# optical_meter_reader_v3.net
KiCad netlist of a schematic drawn in EAGLE
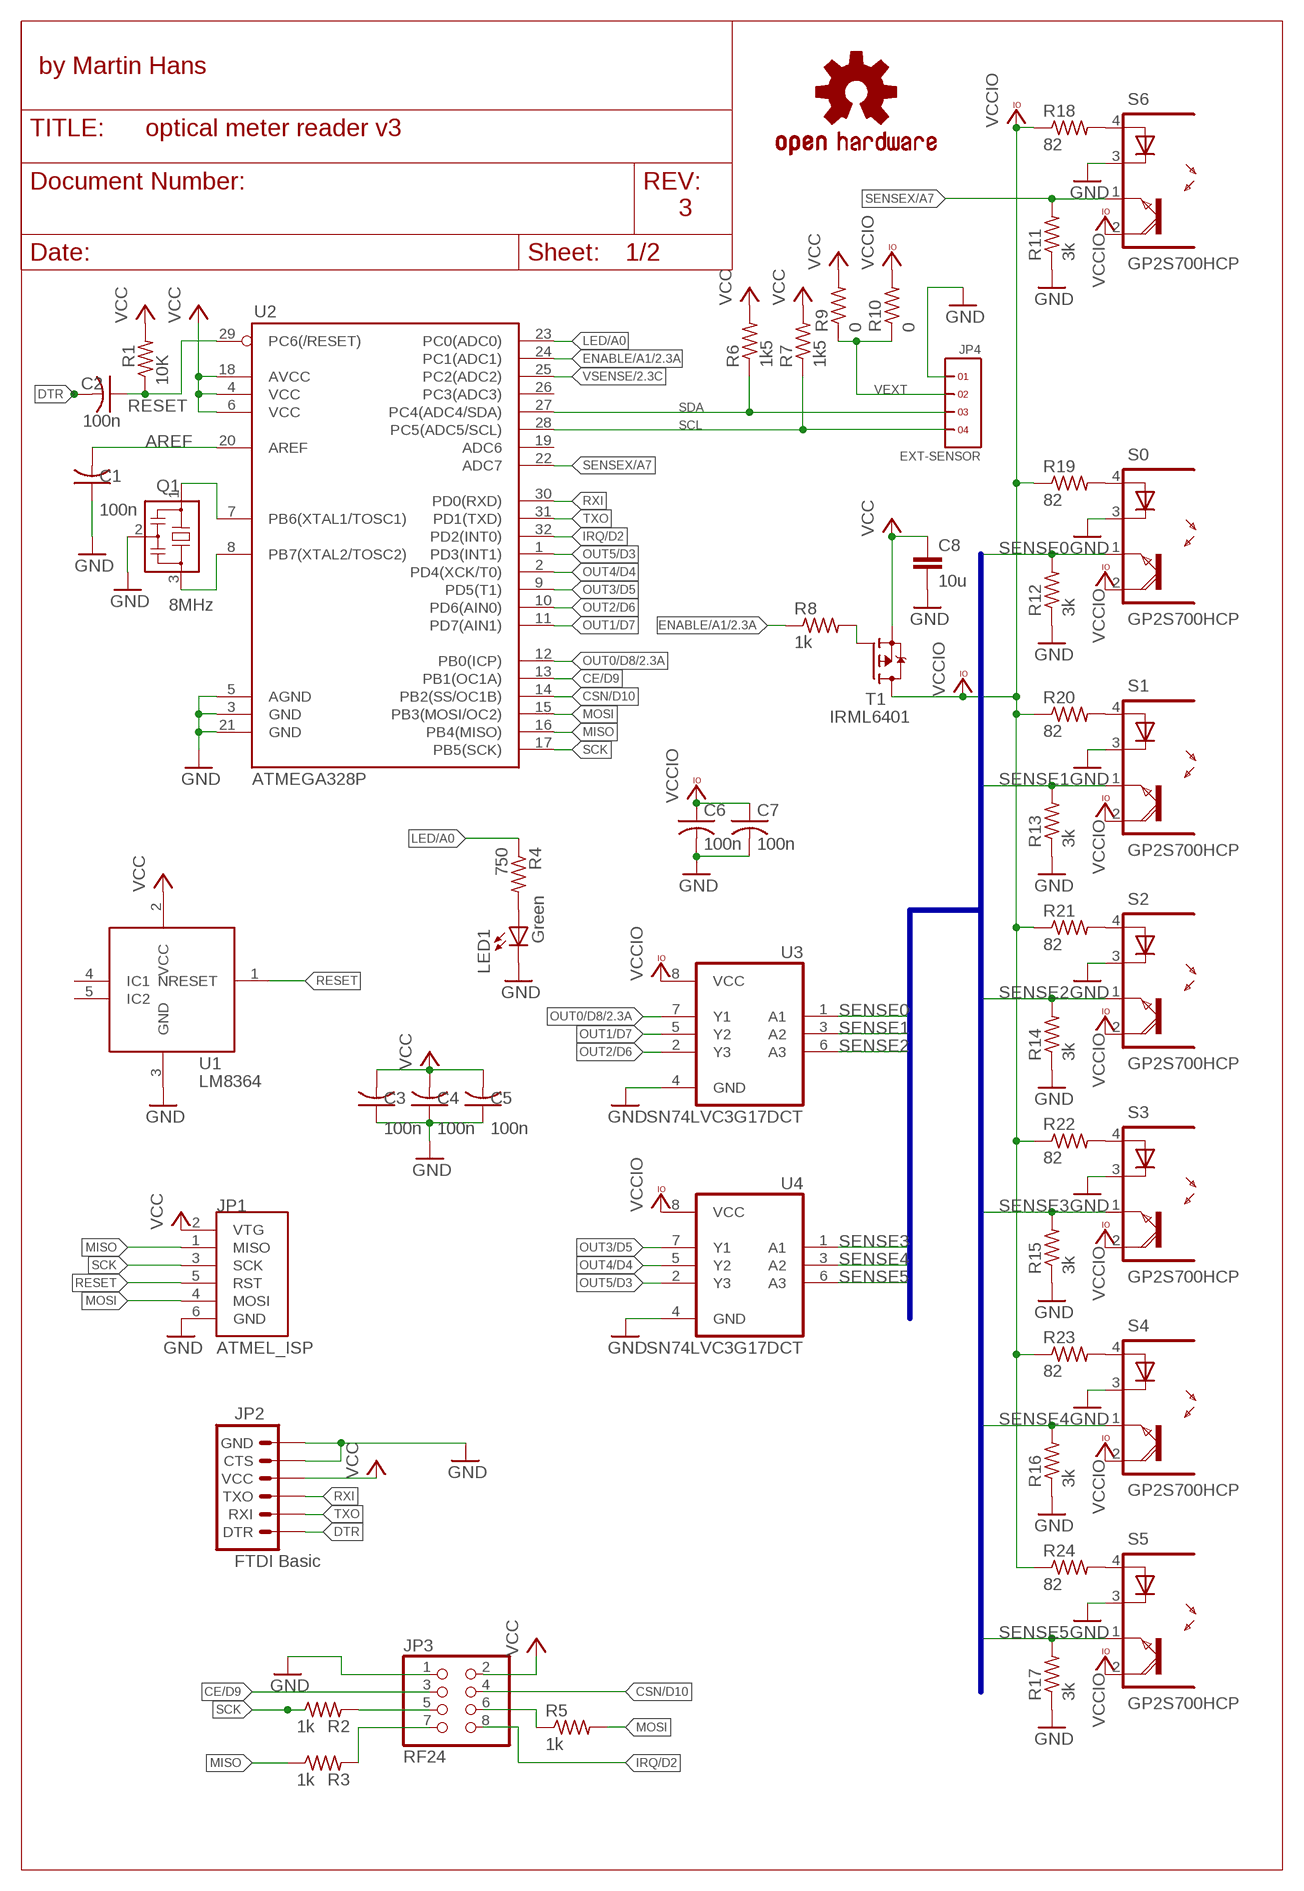
[diagram p0: schematic, sheet 1]
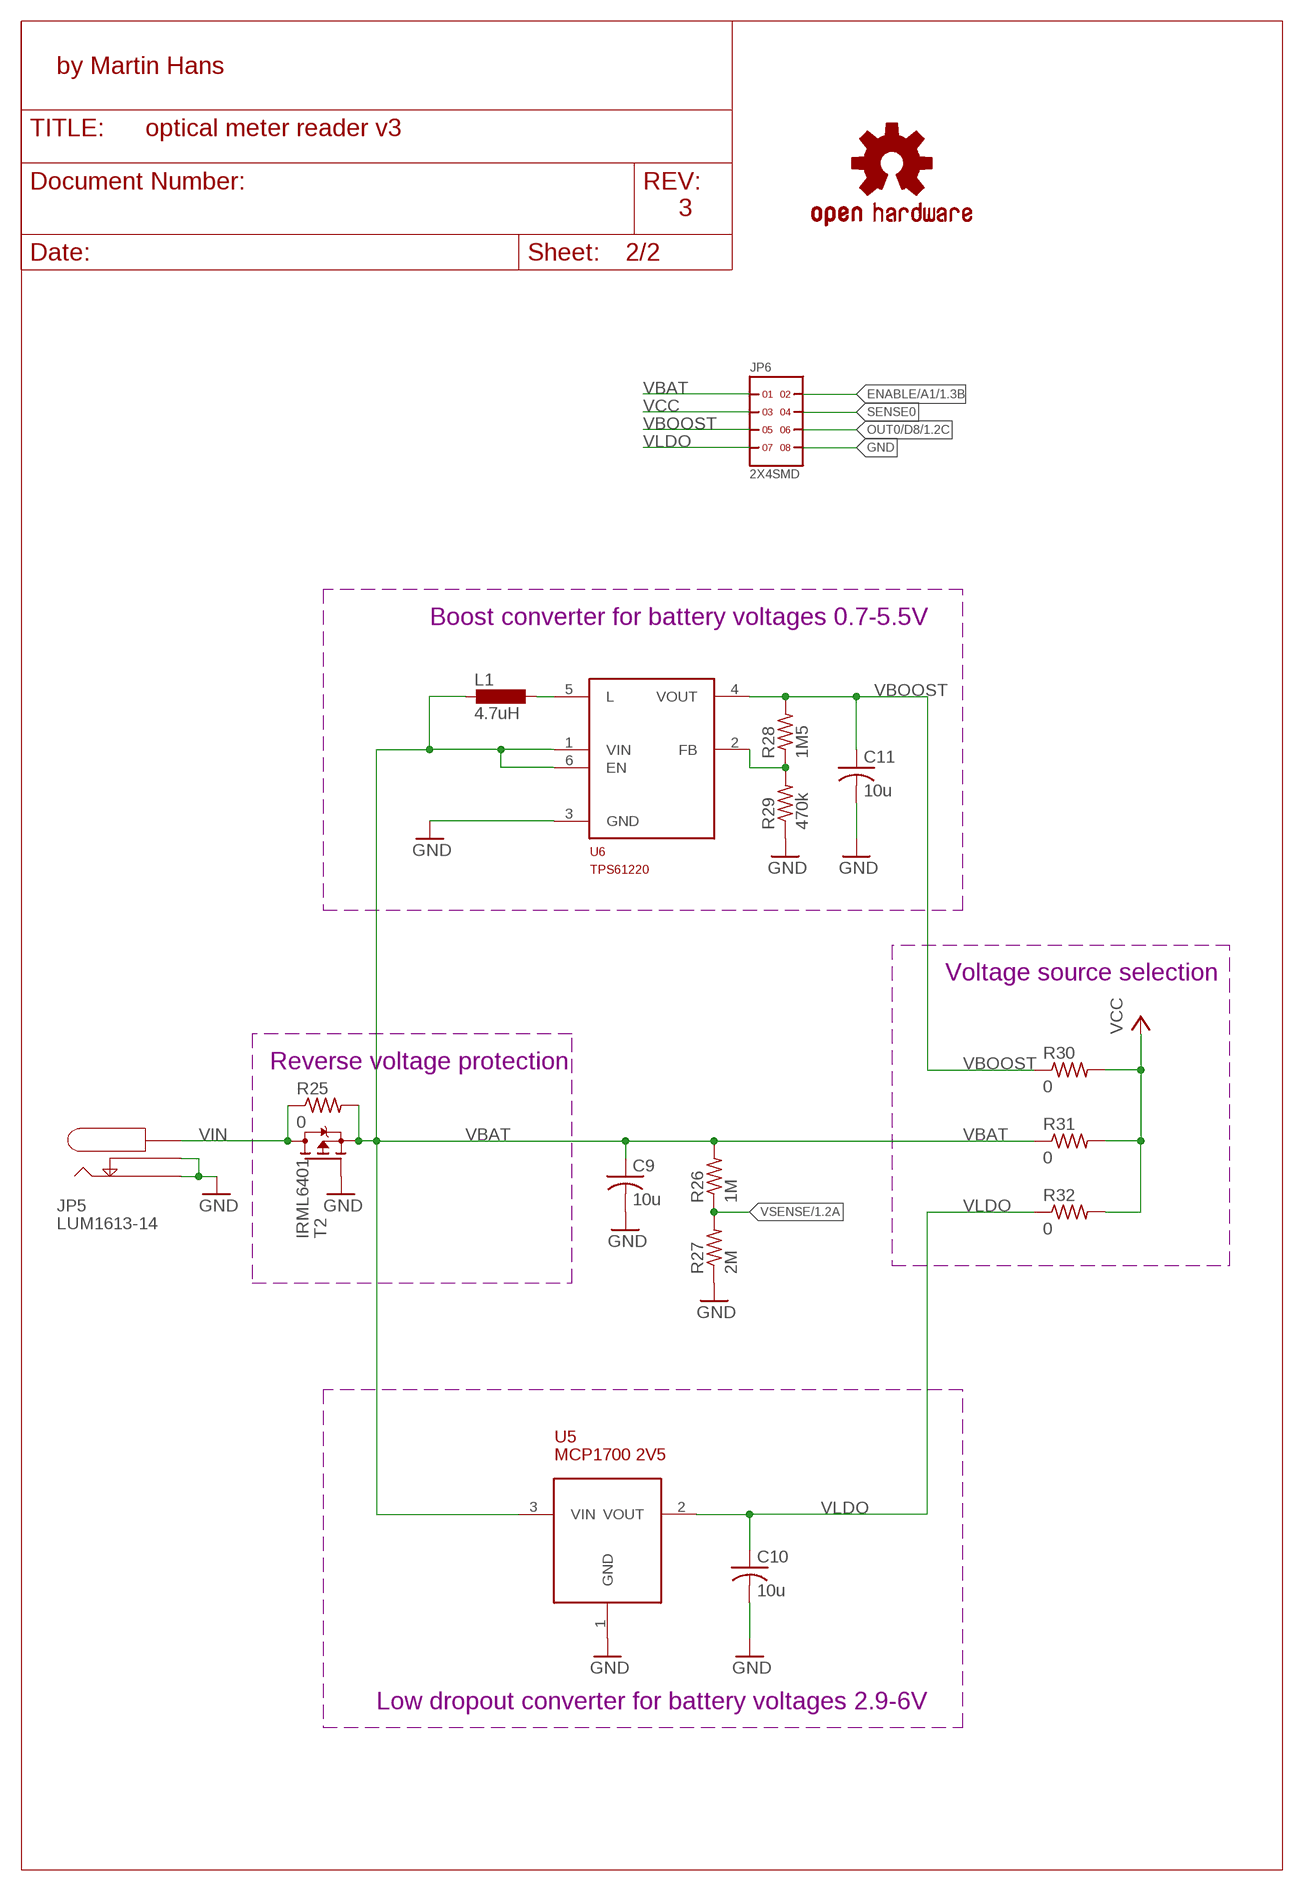
[diagram p1: schematic, sheet 2]

(export (version "E")
  (design (tool "Eeschema 10.0.6"))
  (components
    (comp (ref "C1")
      (value "100n")
      (footprint "eagle-import:C0603")
      (libsource (lib "eagle-import") (part "rcl_C-USC0603"))
    )
    (comp (ref "C2")
      (value "100n")
      (footprint "eagle-import:C0603")
      (libsource (lib "eagle-import") (part "rcl_C-USC0603"))
    )
    (comp (ref "C3")
      (value "100n")
      (footprint "eagle-import:C0603")
      (libsource (lib "eagle-import") (part "rcl_C-USC0603"))
    )
    (comp (ref "C4")
      (value "100n")
      (footprint "eagle-import:C0603")
      (libsource (lib "eagle-import") (part "rcl_C-USC0603"))
    )
    (comp (ref "C5")
      (value "100n")
      (footprint "eagle-import:C0603")
      (libsource (lib "eagle-import") (part "rcl_C-USC0603"))
    )
    (comp (ref "C6")
      (value "100n")
      (footprint "eagle-import:C0603")
      (libsource (lib "eagle-import") (part "rcl_C-USC0603"))
    )
    (comp (ref "C7")
      (value "100n")
      (footprint "eagle-import:C0603")
      (libsource (lib "eagle-import") (part "rcl_C-USC0603"))
    )
    (comp (ref "C8")
      (value "10u")
      (footprint "eagle-import:C0603")
      (libsource (lib "eagle-import") (part "C-EUC0603"))
    )
    (comp (ref "JP1")
      (value "ATMEL_ISP")
      (footprint "eagle-import:2X03")
      (libsource (lib "eagle-import") (part "ATMEL_ISP"))
    )
    (comp (ref "JP2")
      (value "FTDI Basic")
      (footprint "eagle-import:1X06")
      (libsource (lib "eagle-import") (part "ARDUINO_SERIAL_PROGRAMPTH"))
    )
    (comp (ref "JP3")
      (value "RF24")
      (footprint "eagle-import:2X04")
      (libsource (lib "eagle-import") (part "PINHD-2X4"))
    )
    (comp (ref "JP4")
      (value "EXT-SENSOR")
      (footprint "eagle-import:1X4")
      (libsource (lib "eagle-import") (part "1X4"))
    )
    (comp (ref "LED1")
      (value "Green")
      (footprint "eagle-import:0603-LED-ALT1")
      (libsource (lib "eagle-import") (part "LED"))
    )
    (comp (ref "LOGO1")
      (value "OSHW-LOGOL")
      (footprint "eagle-import:OSHW-LOGO-L")
      (libsource (lib "eagle-import") (part "OSHW-LOGOL"))
    )
    (comp (ref "Q1")
      (value "8MHz")
      (footprint "eagle-import:CSTCE")
      (libsource (lib "eagle-import") (part "CSTCE"))
    )
    (comp (ref "R1")
      (value "10K")
      (footprint "eagle-import:R0603")
      (libsource (lib "eagle-import") (part "R-US_R0603"))
    )
    (comp (ref "R2")
      (value "1k")
      (footprint "eagle-import:R0603")
      (libsource (lib "eagle-import") (part "R-US_R0603"))
    )
    (comp (ref "R3")
      (value "1k")
      (footprint "eagle-import:R0603")
      (libsource (lib "eagle-import") (part "R-US_R0603"))
    )
    (comp (ref "R4")
      (value "750")
      (footprint "eagle-import:R0603")
      (libsource (lib "eagle-import") (part "R-US_R0603"))
    )
    (comp (ref "R5")
      (value "1k")
      (footprint "eagle-import:R0603")
      (libsource (lib "eagle-import") (part "R-US_R0603"))
    )
    (comp (ref "R6")
      (value "1k5")
      (footprint "eagle-import:R0603")
      (libsource (lib "eagle-import") (part "R-US_R0603"))
    )
    (comp (ref "R7")
      (value "1k5")
      (footprint "eagle-import:R0603")
      (libsource (lib "eagle-import") (part "R-US_R0603"))
    )
    (comp (ref "R8")
      (value "1k")
      (footprint "eagle-import:R0603")
      (libsource (lib "eagle-import") (part "R-US_R0603"))
    )
    (comp (ref "R9")
      (value "0")
      (footprint "eagle-import:R0603")
      (libsource (lib "eagle-import") (part "R-US_R0603"))
    )
    (comp (ref "R10")
      (value "0")
      (footprint "eagle-import:R0603")
      (libsource (lib "eagle-import") (part "R-US_R0603"))
    )
    (comp (ref "R11")
      (value "3k")
      (footprint "eagle-import:R0603")
      (libsource (lib "eagle-import") (part "R-US_R0603"))
    )
    (comp (ref "R12")
      (value "3k")
      (footprint "eagle-import:R0603")
      (libsource (lib "eagle-import") (part "R-US_R0603"))
    )
    (comp (ref "R13")
      (value "3k")
      (footprint "eagle-import:R0603")
      (libsource (lib "eagle-import") (part "R-US_R0603"))
    )
    (comp (ref "R14")
      (value "3k")
      (footprint "eagle-import:R0603")
      (libsource (lib "eagle-import") (part "R-US_R0603"))
    )
    (comp (ref "R15")
      (value "3k")
      (footprint "eagle-import:R0603")
      (libsource (lib "eagle-import") (part "R-US_R0603"))
    )
    (comp (ref "R16")
      (value "3k")
      (footprint "eagle-import:R0603")
      (libsource (lib "eagle-import") (part "R-US_R0603"))
    )
    (comp (ref "R17")
      (value "3k")
      (footprint "eagle-import:R0603")
      (libsource (lib "eagle-import") (part "R-US_R0603"))
    )
    (comp (ref "R18")
      (value "82")
      (footprint "eagle-import:R0603")
      (libsource (lib "eagle-import") (part "R-US_R0603"))
    )
    (comp (ref "R19")
      (value "82")
      (footprint "eagle-import:R0603")
      (libsource (lib "eagle-import") (part "R-US_R0603"))
    )
    (comp (ref "R20")
      (value "82")
      (footprint "eagle-import:R0603")
      (libsource (lib "eagle-import") (part "R-US_R0603"))
    )
    (comp (ref "R21")
      (value "82")
      (footprint "eagle-import:R0603")
      (libsource (lib "eagle-import") (part "R-US_R0603"))
    )
    (comp (ref "R22")
      (value "82")
      (footprint "eagle-import:R0603")
      (libsource (lib "eagle-import") (part "R-US_R0603"))
    )
    (comp (ref "R23")
      (value "82")
      (footprint "eagle-import:R0603")
      (libsource (lib "eagle-import") (part "R-US_R0603"))
    )
    (comp (ref "R24")
      (value "82")
      (footprint "eagle-import:R0603")
      (libsource (lib "eagle-import") (part "R-US_R0603"))
    )
    (comp (ref "S0")
      (value "GP2S700HCP")
      (footprint "eagle-import:SMD")
      (libsource (lib "eagle-import") (part "GP2S700HCP"))
    )
    (comp (ref "S1")
      (value "GP2S700HCP")
      (footprint "eagle-import:SMD")
      (libsource (lib "eagle-import") (part "GP2S700HCP"))
    )
    (comp (ref "S2")
      (value "GP2S700HCP")
      (footprint "eagle-import:SMD")
      (libsource (lib "eagle-import") (part "GP2S700HCP"))
    )
    (comp (ref "S3")
      (value "GP2S700HCP")
      (footprint "eagle-import:SMD")
      (libsource (lib "eagle-import") (part "GP2S700HCP"))
    )
    (comp (ref "S4")
      (value "GP2S700HCP")
      (footprint "eagle-import:SMD")
      (libsource (lib "eagle-import") (part "GP2S700HCP"))
    )
    (comp (ref "S5")
      (value "GP2S700HCP")
      (footprint "eagle-import:SMD")
      (libsource (lib "eagle-import") (part "GP2S700HCP"))
    )
    (comp (ref "S6")
      (value "GP2S700HCP")
      (footprint "eagle-import:SMD")
      (libsource (lib "eagle-import") (part "GP2S700HCP"))
    )
    (comp (ref "T1")
      (value "IRML6401")
      (footprint "eagle-import:SOT23")
      (libsource (lib "eagle-import") (part "IRML6401"))
    )
    (comp (ref "U1")
      (value "LM8364")
      (footprint "eagle-import:SOT23-DBV")
      (libsource (lib "eagle-import") (part "LM8364"))
    )
    (comp (ref "U2")
      (value "ATMEGA328P")
      (footprint "eagle-import:TQFP32-08")
      (libsource (lib "eagle-import") (part "ATMEGA168"))
    )
    (comp (ref "U3")
      (value "SN74LVC3G17DCT")
      (footprint "eagle-import:SSOP08")
      (libsource (lib "eagle-import") (part "SN743G17DCT"))
    )
    (comp (ref "U4")
      (value "SN74LVC3G17DCT")
      (footprint "eagle-import:SSOP08")
      (libsource (lib "eagle-import") (part "SN743G17DCT"))
    )
    (comp (ref "C9")
      (value "10u")
      (footprint "eagle-import:C0603")
      (libsource (lib "eagle-import") (part "C-USC0603"))
    )
    (comp (ref "C10")
      (value "10u")
      (footprint "eagle-import:C0603")
      (libsource (lib "eagle-import") (part "C-USC0603"))
    )
    (comp (ref "C11")
      (value "10u")
      (footprint "eagle-import:C0603")
      (libsource (lib "eagle-import") (part "C-USC0603"))
    )
    (comp (ref "JP5")
      (value "LUM1613-14")
      (footprint "eagle-import:1613-14")
      (libsource (lib "eagle-import") (part "LUM1613-14"))
    )
    (comp (ref "JP6")
      (value "2X4SMD")
      (footprint "eagle-import:2X4_SMD")
      (libsource (lib "eagle-import") (part "2X4SMD"))
    )
    (comp (ref "L1")
      (value "4.7uH")
      (footprint "eagle-import:EPL3015")
      (libsource (lib "eagle-import") (part "EPL3015"))
    )
    (comp (ref "LOGO2")
      (value "OSHW-LOGOL")
      (footprint "eagle-import:OSHW-LOGO-L")
      (libsource (lib "eagle-import") (part "OSHW-LOGOL"))
    )
    (comp (ref "R25")
      (value "0")
      (footprint "eagle-import:R0603")
      (libsource (lib "eagle-import") (part "R-US_R0603"))
    )
    (comp (ref "R26")
      (value "1M")
      (footprint "eagle-import:R0603")
      (libsource (lib "eagle-import") (part "R-US_R0603"))
    )
    (comp (ref "R27")
      (value "2M")
      (footprint "eagle-import:R0603")
      (libsource (lib "eagle-import") (part "R-US_R0603"))
    )
    (comp (ref "R28")
      (value "1M5")
      (footprint "eagle-import:R0603")
      (libsource (lib "eagle-import") (part "R-US_R0603"))
    )
    (comp (ref "R29")
      (value "470k")
      (footprint "eagle-import:R0603")
      (libsource (lib "eagle-import") (part "R-US_R0603"))
    )
    (comp (ref "R30")
      (value "0")
      (footprint "eagle-import:R0603")
      (libsource (lib "eagle-import") (part "R-US_R0603"))
    )
    (comp (ref "R31")
      (value "0")
      (footprint "eagle-import:R0603")
      (libsource (lib "eagle-import") (part "R-US_R0603"))
    )
    (comp (ref "R32")
      (value "0")
      (footprint "eagle-import:R0603")
      (libsource (lib "eagle-import") (part "R-US_R0603"))
    )
    (comp (ref "T2")
      (value "IRML6401")
      (footprint "eagle-import:SOT23")
      (libsource (lib "eagle-import") (part "IRML6401"))
    )
    (comp (ref "U5")
      (value "MCP1700 2V5")
      (footprint "eagle-import:SOT23")
      (libsource (lib "eagle-import") (part "MCP1700"))
    )
    (comp (ref "U6")
      (value "TPS61220")
      (footprint "eagle-import:DCK-R_PDSO_G6")
      (libsource (lib "eagle-import") (part "TPS61220"))
    )
  )
  (nets
    (net (code "1") (name "AREF") (class "Default")
      (node (ref "C1") (pin "2") (pinfunction "2_2") (pintype "passive"))
      (node (ref "U2") (pin "20") (pinfunction "AREF_20") (pintype "bidirectional"))
    )
    (net (code "2") (name "CE{slash}D9") (class "Default")
      (node (ref "JP3") (pin "3") (pinfunction "3_3") (pintype "passive"))
      (node (ref "U2") (pin "13") (pinfunction "PB1(OC1A)_13") (pintype "bidirectional"))
    )
    (net (code "3") (name "CSN{slash}D10") (class "Default")
      (node (ref "JP3") (pin "4") (pinfunction "4_4") (pintype "passive"))
      (node (ref "U2") (pin "14") (pinfunction "PB2(SS/OC1B)_14") (pintype "bidirectional"))
    )
    (net (code "4") (name "DTR") (class "Default")
      (node (ref "C2") (pin "2") (pinfunction "2_2") (pintype "passive"))
      (node (ref "JP2") (pin "1") (pinfunction "DTR_1") (pintype "passive"))
    )
    (net (code "5") (name "ENABLE{slash}A1") (class "Default")
      (node (ref "JP6") (pin "2") (pinfunction "2_2") (pintype "bidirectional"))
      (node (ref "R8") (pin "1") (pinfunction "1_1") (pintype "passive"))
      (node (ref "U2") (pin "24") (pinfunction "PC1(ADC1)_24") (pintype "bidirectional"))
    )
    (net (code "6") (name "GND") (class "Default")
      (node (ref "C1") (pin "1") (pinfunction "1_1") (pintype "passive"))
      (node (ref "C10") (pin "2") (pinfunction "2_2") (pintype "passive"))
      (node (ref "C11") (pin "2") (pinfunction "2_2") (pintype "passive"))
      (node (ref "C3") (pin "1") (pinfunction "1_1") (pintype "passive"))
      (node (ref "C4") (pin "1") (pinfunction "1_1") (pintype "passive"))
      (node (ref "C5") (pin "1") (pinfunction "1_1") (pintype "passive"))
      (node (ref "C6") (pin "2") (pinfunction "2_2") (pintype "passive"))
      (node (ref "C7") (pin "2") (pinfunction "2_2") (pintype "passive"))
      (node (ref "C8") (pin "2") (pinfunction "2_2") (pintype "passive"))
      (node (ref "C9") (pin "2") (pinfunction "2_2") (pintype "passive"))
      (node (ref "JP1") (pin "6") (pinfunction "GND_6") (pintype "bidirectional"))
      (node (ref "JP2") (pin "5") (pinfunction "CTS_5") (pintype "passive"))
      (node (ref "JP2") (pin "6") (pinfunction "GND_6") (pintype "passive"))
      (node (ref "JP3") (pin "1") (pinfunction "1_1") (pintype "passive"))
      (node (ref "JP4") (pin "1") (pinfunction "1_1") (pintype "bidirectional"))
      (node (ref "JP5") (pin "1") (pinfunction "SHIELD_1") (pintype "bidirectional"))
      (node (ref "JP5") (pin "2") (pinfunction "CONNECT_2") (pintype "bidirectional"))
      (node (ref "JP6") (pin "8") (pinfunction "8_8") (pintype "bidirectional"))
      (node (ref "LED1") (pin "C") (pinfunction "C_C") (pintype "passive"))
      (node (ref "Q1") (pin "2") (pinfunction "2_2") (pintype "passive"))
      (node (ref "R11") (pin "1") (pinfunction "1_1") (pintype "passive"))
      (node (ref "R12") (pin "1") (pinfunction "1_1") (pintype "passive"))
      (node (ref "R13") (pin "1") (pinfunction "1_1") (pintype "passive"))
      (node (ref "R14") (pin "1") (pinfunction "1_1") (pintype "passive"))
      (node (ref "R15") (pin "1") (pinfunction "1_1") (pintype "passive"))
      (node (ref "R16") (pin "1") (pinfunction "1_1") (pintype "passive"))
      (node (ref "R17") (pin "1") (pinfunction "1_1") (pintype "passive"))
      (node (ref "R27") (pin "1") (pinfunction "1_1") (pintype "passive"))
      (node (ref "R29") (pin "1") (pinfunction "1_1") (pintype "passive"))
      (node (ref "S0") (pin "3") (pinfunction "C_3") (pintype "passive"))
      (node (ref "S1") (pin "3") (pinfunction "C_3") (pintype "passive"))
      (node (ref "S2") (pin "3") (pinfunction "C_3") (pintype "passive"))
      (node (ref "S3") (pin "3") (pinfunction "C_3") (pintype "passive"))
      (node (ref "S4") (pin "3") (pinfunction "C_3") (pintype "passive"))
      (node (ref "S5") (pin "3") (pinfunction "C_3") (pintype "passive"))
      (node (ref "S6") (pin "3") (pinfunction "C_3") (pintype "passive"))
      (node (ref "T2") (pin "1") (pinfunction "G_1") (pintype "passive"))
      (node (ref "U1") (pin "3") (pinfunction "GND_3") (pintype "bidirectional"))
      (node (ref "U2") (pin "21") (pinfunction "GND_21") (pintype "bidirectional"))
      (node (ref "U2") (pin "3") (pinfunction "GND_3") (pintype "bidirectional"))
      (node (ref "U2") (pin "5") (pinfunction "AGND_5") (pintype "bidirectional"))
      (node (ref "U3") (pin "4") (pinfunction "GND_4") (pintype "power_in"))
      (node (ref "U4") (pin "4") (pinfunction "GND_4") (pintype "power_in"))
      (node (ref "U5") (pin "1") (pinfunction "GND_1") (pintype "bidirectional"))
      (node (ref "U6") (pin "3") (pinfunction "GND_3") (pintype "bidirectional"))
    )
    (net (code "7") (name "IRQ{slash}D2") (class "Default")
      (node (ref "JP3") (pin "8") (pinfunction "8_8") (pintype "passive"))
      (node (ref "U2") (pin "32") (pinfunction "PD2(INT0)_32") (pintype "bidirectional"))
    )
    (net (code "8") (name "LED{slash}A0") (class "Default")
      (node (ref "R4") (pin "1") (pinfunction "1_1") (pintype "passive"))
      (node (ref "U2") (pin "23") (pinfunction "PC0(ADC0)_23") (pintype "bidirectional"))
    )
    (net (code "9") (name "MISO") (class "Default")
      (node (ref "JP1") (pin "1") (pinfunction "MISO_1") (pintype "bidirectional"))
      (node (ref "R3") (pin "1") (pinfunction "1_1") (pintype "passive"))
      (node (ref "U2") (pin "16") (pinfunction "PB4(MISO)_16") (pintype "bidirectional"))
    )
    (net (code "10") (name "MOSI") (class "Default")
      (node (ref "JP1") (pin "4") (pinfunction "MOSI_4") (pintype "bidirectional"))
      (node (ref "R5") (pin "2") (pinfunction "2_2") (pintype "passive"))
      (node (ref "U2") (pin "15") (pinfunction "PB3(MOSI/OC2)_15") (pintype "bidirectional"))
    )
    (net (code "11") (name "Net-(JP3-Pad5)") (class "Default")
      (node (ref "JP3") (pin "5") (pinfunction "5_5") (pintype "passive"))
      (node (ref "R2") (pin "2") (pinfunction "2_2") (pintype "passive"))
    )
    (net (code "12") (name "Net-(JP3-Pad6)") (class "Default")
      (node (ref "JP3") (pin "6") (pinfunction "6_6") (pintype "passive"))
      (node (ref "R5") (pin "1") (pinfunction "1_1") (pintype "passive"))
    )
    (net (code "13") (name "Net-(JP3-Pad7)") (class "Default")
      (node (ref "JP3") (pin "7") (pinfunction "7_7") (pintype "passive"))
      (node (ref "R3") (pin "2") (pinfunction "2_2") (pintype "passive"))
    )
    (net (code "14") (name "Net-(L1-2)") (class "Default")
      (node (ref "L1") (pin "P$2") (pinfunction "2_P$2") (pintype "passive"))
      (node (ref "U6") (pin "5") (pinfunction "L_5") (pintype "bidirectional"))
    )
    (net (code "15") (name "Net-(LED1-PadA)") (class "Default")
      (node (ref "LED1") (pin "A") (pinfunction "A_A") (pintype "passive"))
      (node (ref "R4") (pin "2") (pinfunction "2_2") (pintype "passive"))
    )
    (net (code "16") (name "Net-(S0-A)") (class "Default")
      (node (ref "R19") (pin "2") (pinfunction "2_2") (pintype "passive"))
      (node (ref "S0") (pin "4") (pinfunction "A_4") (pintype "passive"))
    )
    (net (code "17") (name "Net-(S1-A)") (class "Default")
      (node (ref "R20") (pin "2") (pinfunction "2_2") (pintype "passive"))
      (node (ref "S1") (pin "4") (pinfunction "A_4") (pintype "passive"))
    )
    (net (code "18") (name "Net-(S2-A)") (class "Default")
      (node (ref "R21") (pin "2") (pinfunction "2_2") (pintype "passive"))
      (node (ref "S2") (pin "4") (pinfunction "A_4") (pintype "passive"))
    )
    (net (code "19") (name "Net-(S3-A)") (class "Default")
      (node (ref "R22") (pin "2") (pinfunction "2_2") (pintype "passive"))
      (node (ref "S3") (pin "4") (pinfunction "A_4") (pintype "passive"))
    )
    (net (code "20") (name "Net-(S4-A)") (class "Default")
      (node (ref "R23") (pin "2") (pinfunction "2_2") (pintype "passive"))
      (node (ref "S4") (pin "4") (pinfunction "A_4") (pintype "passive"))
    )
    (net (code "21") (name "Net-(S5-A)") (class "Default")
      (node (ref "R24") (pin "2") (pinfunction "2_2") (pintype "passive"))
      (node (ref "S5") (pin "4") (pinfunction "A_4") (pintype "passive"))
    )
    (net (code "22") (name "Net-(S6-A)") (class "Default")
      (node (ref "R18") (pin "2") (pinfunction "2_2") (pintype "passive"))
      (node (ref "S6") (pin "4") (pinfunction "A_4") (pintype "passive"))
    )
    (net (code "23") (name "Net-(T1-G)") (class "Default")
      (node (ref "R8") (pin "2") (pinfunction "2_2") (pintype "passive"))
      (node (ref "T1") (pin "1") (pinfunction "G_1") (pintype "passive"))
    )
    (net (code "24") (name "Net-(U2-PB6(XTAL1{slash}TOSC1))") (class "Default")
      (node (ref "Q1") (pin "1") (pinfunction "1_1") (pintype "passive"))
      (node (ref "U2") (pin "7") (pinfunction "PB6(XTAL1/TOSC1)_7") (pintype "bidirectional"))
    )
    (net (code "25") (name "Net-(U2-PB7(XTAL2{slash}TOSC2))") (class "Default")
      (node (ref "Q1") (pin "3") (pinfunction "3_3") (pintype "passive"))
      (node (ref "U2") (pin "8") (pinfunction "PB7(XTAL2/TOSC2)_8") (pintype "bidirectional"))
    )
    (net (code "26") (name "Net-(U6-FB)") (class "Default")
      (node (ref "R28") (pin "1") (pinfunction "1_1") (pintype "passive"))
      (node (ref "R29") (pin "2") (pinfunction "2_2") (pintype "passive"))
      (node (ref "U6") (pin "2") (pinfunction "FB_2") (pintype "bidirectional"))
    )
    (net (code "27") (name "OUT0{slash}D8") (class "Default")
      (node (ref "JP6") (pin "6") (pinfunction "6_6") (pintype "bidirectional"))
      (node (ref "U2") (pin "12") (pinfunction "PB0(ICP)_12") (pintype "bidirectional"))
      (node (ref "U3") (pin "7") (pinfunction "Y1_7") (pintype "tri_state"))
    )
    (net (code "28") (name "OUT1{slash}D7") (class "Default")
      (node (ref "U2") (pin "11") (pinfunction "PD7(AIN1)_11") (pintype "bidirectional"))
      (node (ref "U3") (pin "5") (pinfunction "Y2_5") (pintype "tri_state"))
    )
    (net (code "29") (name "OUT2{slash}D6") (class "Default")
      (node (ref "U2") (pin "10") (pinfunction "PD6(AIN0)_10") (pintype "bidirectional"))
      (node (ref "U3") (pin "2") (pinfunction "Y3_2") (pintype "tri_state"))
    )
    (net (code "30") (name "OUT3{slash}D5") (class "Default")
      (node (ref "U2") (pin "9") (pinfunction "PD5(T1)_9") (pintype "bidirectional"))
      (node (ref "U4") (pin "7") (pinfunction "Y1_7") (pintype "tri_state"))
    )
    (net (code "31") (name "OUT4{slash}D4") (class "Default")
      (node (ref "U2") (pin "2") (pinfunction "PD4(XCK/T0)_2") (pintype "bidirectional"))
      (node (ref "U4") (pin "5") (pinfunction "Y2_5") (pintype "tri_state"))
    )
    (net (code "32") (name "OUT5{slash}D3") (class "Default")
      (node (ref "U2") (pin "1") (pinfunction "PD3(INT1)_1") (pintype "bidirectional"))
      (node (ref "U4") (pin "2") (pinfunction "Y3_2") (pintype "tri_state"))
    )
    (net (code "33") (name "RESET") (class "Default")
      (node (ref "C2") (pin "1") (pinfunction "1_1") (pintype "passive"))
      (node (ref "JP1") (pin "5") (pinfunction "RST_5") (pintype "bidirectional"))
      (node (ref "R1") (pin "1") (pinfunction "1_1") (pintype "passive"))
      (node (ref "U1") (pin "1") (pinfunction "NRESET_1") (pintype "output"))
      (node (ref "U2") (pin "29") (pinfunction "PC6(/RESET)_29") (pintype "bidirectional"))
    )
    (net (code "34") (name "RXI") (class "Default")
      (node (ref "JP2") (pin "3") (pinfunction "TXO_3") (pintype "passive"))
      (node (ref "U2") (pin "30") (pinfunction "PD0(RXD)_30") (pintype "bidirectional"))
    )
    (net (code "35") (name "SCK") (class "Default")
      (node (ref "JP1") (pin "3") (pinfunction "SCK_3") (pintype "bidirectional"))
      (node (ref "R2") (pin "1") (pinfunction "1_1") (pintype "passive"))
      (node (ref "U2") (pin "17") (pinfunction "PB5(SCK)_17") (pintype "bidirectional"))
    )
    (net (code "36") (name "SCL") (class "Default")
      (node (ref "JP4") (pin "4") (pinfunction "4_4") (pintype "bidirectional"))
      (node (ref "R7") (pin "1") (pinfunction "1_1") (pintype "passive"))
      (node (ref "U2") (pin "28") (pinfunction "PC5(ADC5/SCL)_28") (pintype "bidirectional"))
    )
    (net (code "37") (name "SDA") (class "Default")
      (node (ref "JP4") (pin "3") (pinfunction "3_3") (pintype "bidirectional"))
      (node (ref "R6") (pin "1") (pinfunction "1_1") (pintype "passive"))
      (node (ref "U2") (pin "27") (pinfunction "PC4(ADC4/SDA)_27") (pintype "bidirectional"))
    )
    (net (code "38") (name "SENSE0") (class "Default")
      (node (ref "JP6") (pin "4") (pinfunction "4_4") (pintype "bidirectional"))
      (node (ref "R12") (pin "2") (pinfunction "2_2") (pintype "passive"))
      (node (ref "S0") (pin "1") (pinfunction "EMI_1") (pintype "passive"))
      (node (ref "U3") (pin "1") (pinfunction "A1_1") (pintype "tri_state"))
    )
    (net (code "39") (name "SENSE1") (class "Default")
      (node (ref "R13") (pin "2") (pinfunction "2_2") (pintype "passive"))
      (node (ref "S1") (pin "1") (pinfunction "EMI_1") (pintype "passive"))
      (node (ref "U3") (pin "3") (pinfunction "A2_3") (pintype "tri_state"))
    )
    (net (code "40") (name "SENSE2") (class "Default")
      (node (ref "R14") (pin "2") (pinfunction "2_2") (pintype "passive"))
      (node (ref "S2") (pin "1") (pinfunction "EMI_1") (pintype "passive"))
      (node (ref "U3") (pin "6") (pinfunction "A3_6") (pintype "tri_state"))
    )
    (net (code "41") (name "SENSE3") (class "Default")
      (node (ref "R15") (pin "2") (pinfunction "2_2") (pintype "passive"))
      (node (ref "S3") (pin "1") (pinfunction "EMI_1") (pintype "passive"))
      (node (ref "U4") (pin "1") (pinfunction "A1_1") (pintype "tri_state"))
    )
    (net (code "42") (name "SENSE4") (class "Default")
      (node (ref "R16") (pin "2") (pinfunction "2_2") (pintype "passive"))
      (node (ref "S4") (pin "1") (pinfunction "EMI_1") (pintype "passive"))
      (node (ref "U4") (pin "3") (pinfunction "A2_3") (pintype "tri_state"))
    )
    (net (code "43") (name "SENSE5") (class "Default")
      (node (ref "R17") (pin "2") (pinfunction "2_2") (pintype "passive"))
      (node (ref "S5") (pin "1") (pinfunction "EMI_1") (pintype "passive"))
      (node (ref "U4") (pin "6") (pinfunction "A3_6") (pintype "tri_state"))
    )
    (net (code "44") (name "SENSEX{slash}A7") (class "Default")
      (node (ref "R11") (pin "2") (pinfunction "2_2") (pintype "passive"))
      (node (ref "S6") (pin "1") (pinfunction "EMI_1") (pintype "passive"))
      (node (ref "U2") (pin "22") (pinfunction "ADC7_22") (pintype "bidirectional"))
    )
    (net (code "45") (name "TXO") (class "Default")
      (node (ref "JP2") (pin "2") (pinfunction "RXI_2") (pintype "passive"))
      (node (ref "U2") (pin "31") (pinfunction "PD1(TXD)_31") (pintype "bidirectional"))
    )
    (net (code "46") (name "VBAT") (class "Default")
      (node (ref "C9") (pin "1") (pinfunction "1_1") (pintype "passive"))
      (node (ref "JP6") (pin "1") (pinfunction "1_1") (pintype "bidirectional"))
      (node (ref "L1") (pin "P$1") (pinfunction "1_P$1") (pintype "passive"))
      (node (ref "R25") (pin "2") (pinfunction "2_2") (pintype "passive"))
      (node (ref "R26") (pin "2") (pinfunction "2_2") (pintype "passive"))
      (node (ref "R31") (pin "1") (pinfunction "1_1") (pintype "passive"))
      (node (ref "T2") (pin "2") (pinfunction "S_2") (pintype "passive"))
      (node (ref "U5") (pin "3") (pinfunction "VIN_3") (pintype "bidirectional"))
      (node (ref "U6") (pin "1") (pinfunction "VIN_1") (pintype "bidirectional"))
      (node (ref "U6") (pin "6") (pinfunction "EN_6") (pintype "bidirectional"))
    )
    (net (code "47") (name "VBOOST") (class "Default")
      (node (ref "C11") (pin "1") (pinfunction "1_1") (pintype "passive"))
      (node (ref "JP6") (pin "5") (pinfunction "5_5") (pintype "bidirectional"))
      (node (ref "R28") (pin "2") (pinfunction "2_2") (pintype "passive"))
      (node (ref "R30") (pin "1") (pinfunction "1_1") (pintype "passive"))
      (node (ref "U6") (pin "4") (pinfunction "VOUT_4") (pintype "bidirectional"))
    )
    (net (code "48") (name "VCC") (class "Default")
      (node (ref "C3") (pin "2") (pinfunction "2_2") (pintype "passive"))
      (node (ref "C4") (pin "2") (pinfunction "2_2") (pintype "passive"))
      (node (ref "C5") (pin "2") (pinfunction "2_2") (pintype "passive"))
      (node (ref "C8") (pin "1") (pinfunction "1_1") (pintype "passive"))
      (node (ref "JP1") (pin "2") (pinfunction "VTG_2") (pintype "bidirectional"))
      (node (ref "JP2") (pin "4") (pinfunction "VCC_4") (pintype "passive"))
      (node (ref "JP3") (pin "2") (pinfunction "2_2") (pintype "passive"))
      (node (ref "JP6") (pin "3") (pinfunction "3_3") (pintype "bidirectional"))
      (node (ref "R1") (pin "2") (pinfunction "2_2") (pintype "passive"))
      (node (ref "R30") (pin "2") (pinfunction "2_2") (pintype "passive"))
      (node (ref "R31") (pin "2") (pinfunction "2_2") (pintype "passive"))
      (node (ref "R32") (pin "2") (pinfunction "2_2") (pintype "passive"))
      (node (ref "R6") (pin "2") (pinfunction "2_2") (pintype "passive"))
      (node (ref "R7") (pin "2") (pinfunction "2_2") (pintype "passive"))
      (node (ref "R9") (pin "2") (pinfunction "2_2") (pintype "passive"))
      (node (ref "T1") (pin "2") (pinfunction "S_2") (pintype "passive"))
      (node (ref "U1") (pin "2") (pinfunction "VCC_2") (pintype "bidirectional"))
      (node (ref "U2") (pin "18") (pinfunction "AVCC_18") (pintype "bidirectional"))
      (node (ref "U2") (pin "4") (pinfunction "VCC_4") (pintype "bidirectional"))
      (node (ref "U2") (pin "6") (pinfunction "VCC_6") (pintype "bidirectional"))
    )
    (net (code "49") (name "VCCIO") (class "Default")
      (node (ref "C6") (pin "1") (pinfunction "1_1") (pintype "passive"))
      (node (ref "C7") (pin "1") (pinfunction "1_1") (pintype "passive"))
      (node (ref "R10") (pin "2") (pinfunction "2_2") (pintype "passive"))
      (node (ref "R18") (pin "1") (pinfunction "1_1") (pintype "passive"))
      (node (ref "R19") (pin "1") (pinfunction "1_1") (pintype "passive"))
      (node (ref "R20") (pin "1") (pinfunction "1_1") (pintype "passive"))
      (node (ref "R21") (pin "1") (pinfunction "1_1") (pintype "passive"))
      (node (ref "R22") (pin "1") (pinfunction "1_1") (pintype "passive"))
      (node (ref "R23") (pin "1") (pinfunction "1_1") (pintype "passive"))
      (node (ref "R24") (pin "1") (pinfunction "1_1") (pintype "passive"))
      (node (ref "S0") (pin "2") (pinfunction "COL_2") (pintype "passive"))
      (node (ref "S1") (pin "2") (pinfunction "COL_2") (pintype "passive"))
      (node (ref "S2") (pin "2") (pinfunction "COL_2") (pintype "passive"))
      (node (ref "S3") (pin "2") (pinfunction "COL_2") (pintype "passive"))
      (node (ref "S4") (pin "2") (pinfunction "COL_2") (pintype "passive"))
      (node (ref "S5") (pin "2") (pinfunction "COL_2") (pintype "passive"))
      (node (ref "S6") (pin "2") (pinfunction "COL_2") (pintype "passive"))
      (node (ref "T1") (pin "3") (pinfunction "D_3") (pintype "passive"))
      (node (ref "U3") (pin "8") (pinfunction "VCC_8") (pintype "power_in"))
      (node (ref "U4") (pin "8") (pinfunction "VCC_8") (pintype "power_in"))
    )
    (net (code "50") (name "VEXT") (class "Default")
      (node (ref "JP4") (pin "2") (pinfunction "2_2") (pintype "bidirectional"))
      (node (ref "R10") (pin "1") (pinfunction "1_1") (pintype "passive"))
      (node (ref "R9") (pin "1") (pinfunction "1_1") (pintype "passive"))
    )
    (net (code "51") (name "VIN") (class "Default")
      (node (ref "JP5") (pin "3@1") (pinfunction "CENTER_3@1") (pintype "bidirectional"))
      (node (ref "JP5") (pin "3@2") (pinfunction "CENTER_3@2") (pintype "bidirectional"))
      (node (ref "R25") (pin "1") (pinfunction "1_1") (pintype "passive"))
      (node (ref "T2") (pin "3") (pinfunction "D_3") (pintype "passive"))
    )
    (net (code "52") (name "VLDO") (class "Default")
      (node (ref "C10") (pin "1") (pinfunction "1_1") (pintype "passive"))
      (node (ref "JP6") (pin "7") (pinfunction "7_7") (pintype "bidirectional"))
      (node (ref "R32") (pin "1") (pinfunction "1_1") (pintype "passive"))
      (node (ref "U5") (pin "2") (pinfunction "VOUT_2") (pintype "bidirectional"))
    )
    (net (code "53") (name "VSENSE") (class "Default")
      (node (ref "R26") (pin "1") (pinfunction "1_1") (pintype "passive"))
      (node (ref "R27") (pin "2") (pinfunction "2_2") (pintype "passive"))
      (node (ref "U2") (pin "25") (pinfunction "PC2(ADC2)_25") (pintype "bidirectional"))
    )
    (net (code "54") (name "unconnected-(U1-IC1-Pad4)") (class "Default")
      (node (ref "U1") (pin "4") (pinfunction "IC1_4") (pintype "bidirectional"))
    )
    (net (code "55") (name "unconnected-(U1-IC2-Pad5)") (class "Default")
      (node (ref "U1") (pin "5") (pinfunction "IC2_5") (pintype "bidirectional"))
    )
    (net (code "56") (name "unconnected-(U2-ADC6-Pad19)") (class "Default")
      (node (ref "U2") (pin "19") (pinfunction "ADC6_19") (pintype "bidirectional"))
    )
    (net (code "57") (name "unconnected-(U2-PC3(ADC3)-Pad26)") (class "Default")
      (node (ref "U2") (pin "26") (pinfunction "PC3(ADC3)_26") (pintype "bidirectional"))
    )
  )
)
